# RS485_Port.net
KiCad netlist of a schematic drawn in Altium Designer
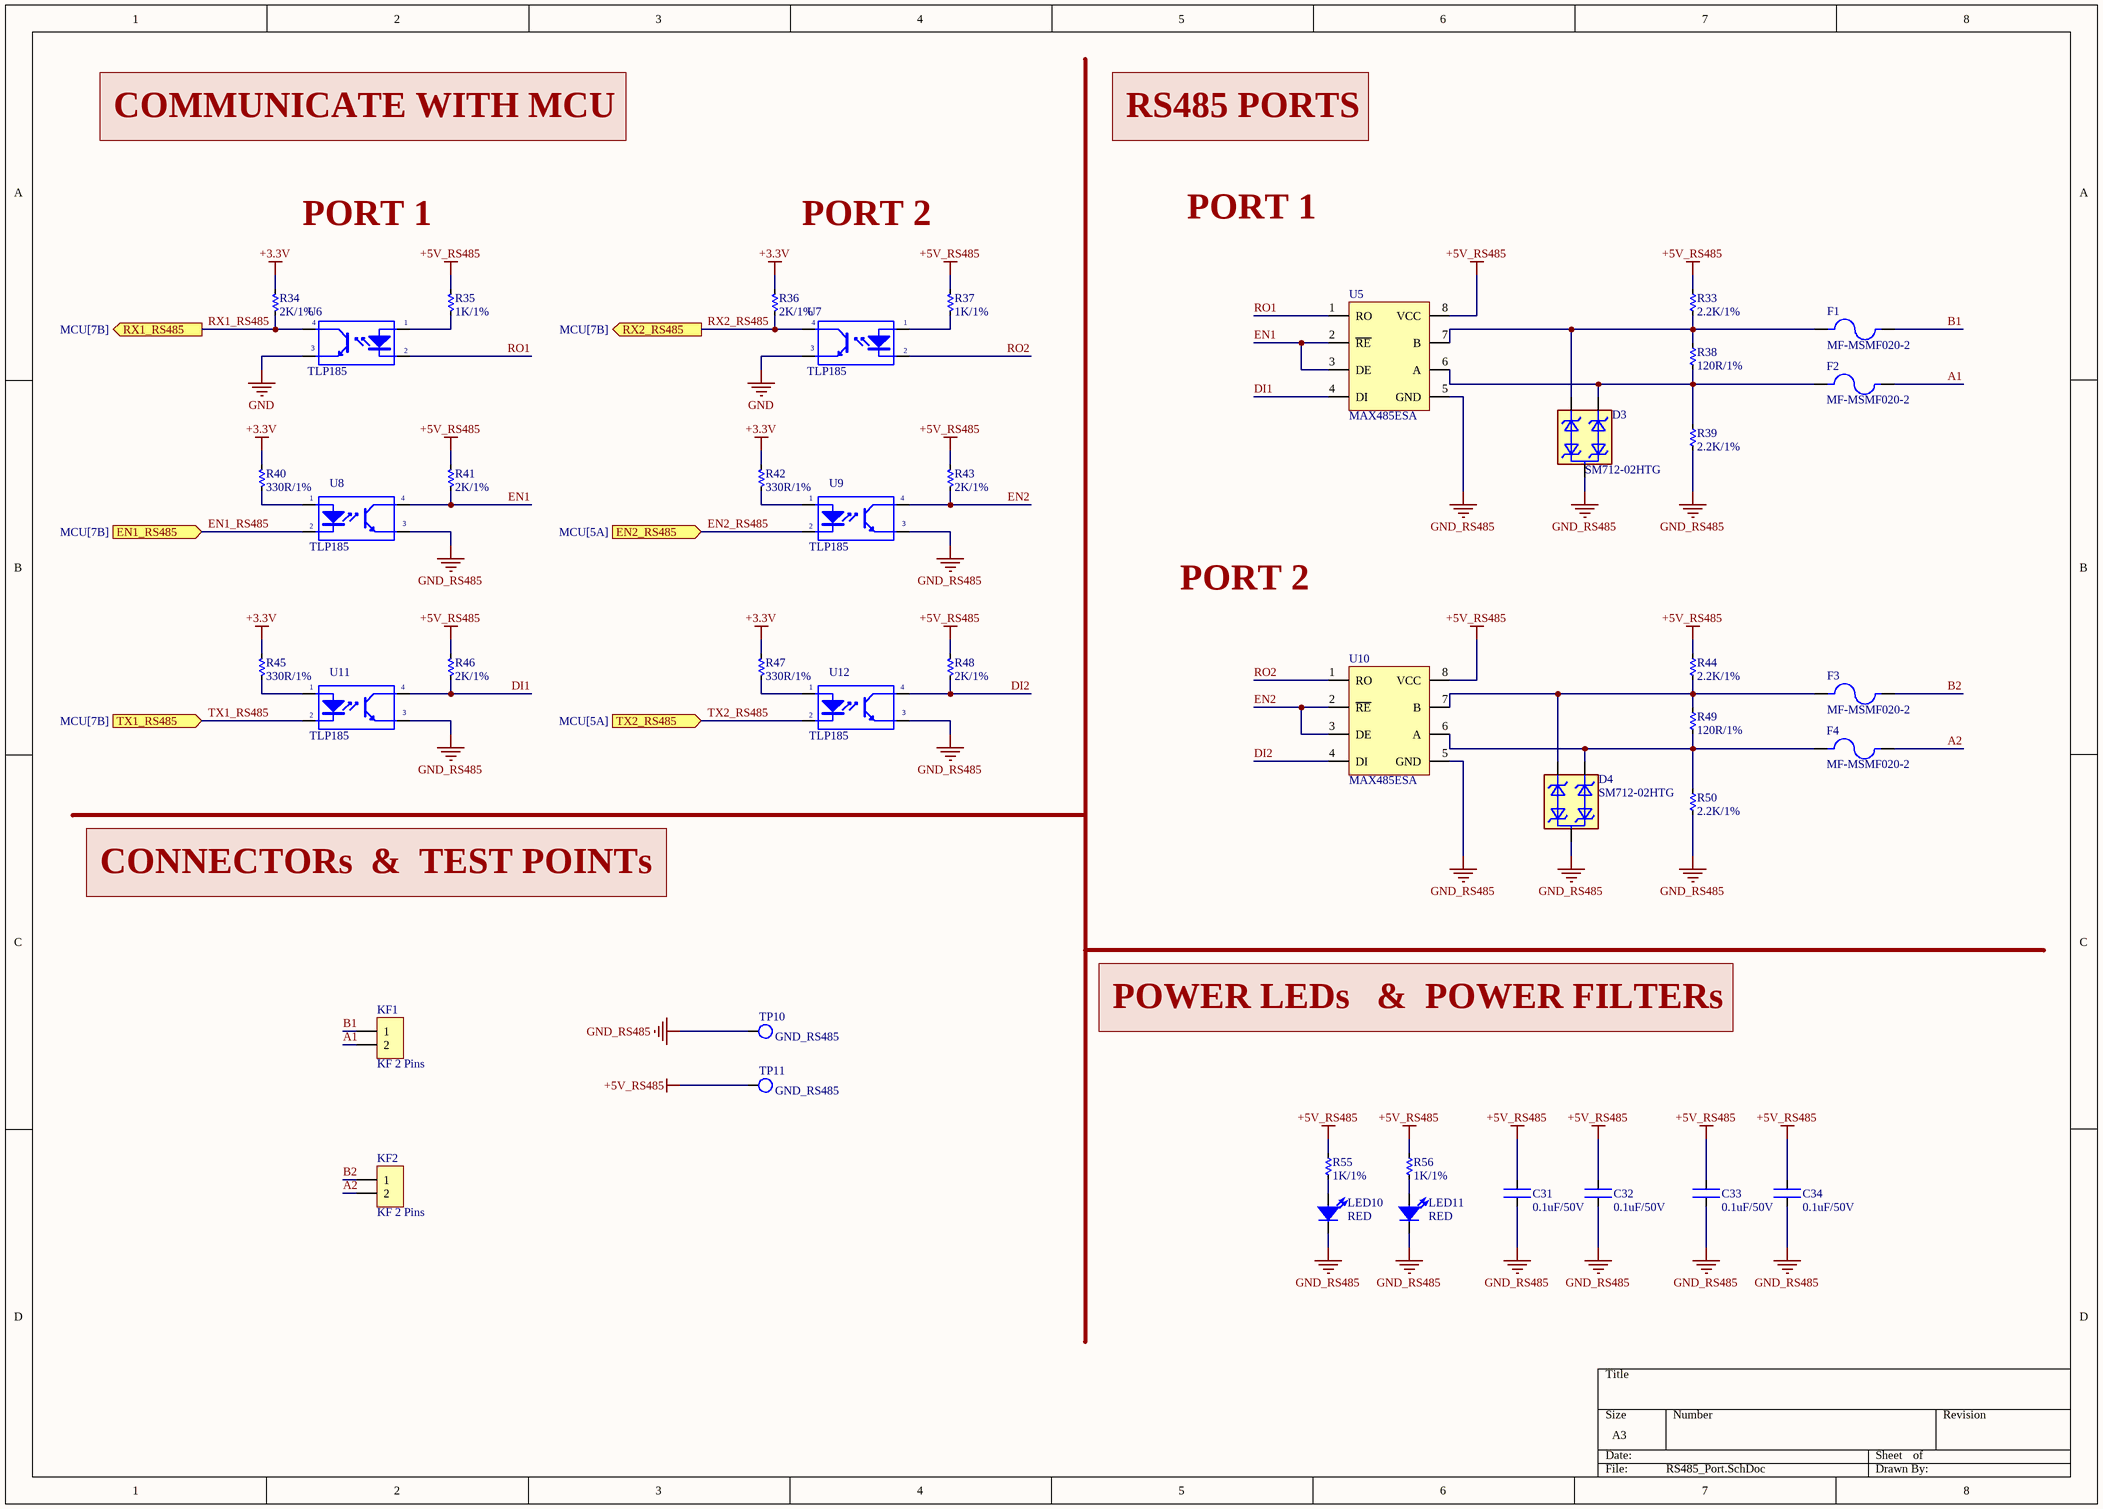
[diagram p0: RS485_Port.SchDoc]

(export (version "E")
  (design (tool "Eeschema 10.0.6"))
  (components
    (comp (ref "C31")
      (value "0.1uF/50V")
      (footprint "CAP - 0603")
      (description "CAPACITOR SMD - KEMET")
      (libsource (lib "NewLibrary") (part "CAPACITOR"))
    )
    (comp (ref "C32")
      (value "0.1uF/50V")
      (footprint "CAP - 0603")
      (description "CAPACITOR SMD - KEMET")
      (libsource (lib "NewLibrary") (part "CAPACITOR"))
    )
    (comp (ref "C33")
      (value "0.1uF/50V")
      (footprint "CAP - 0603")
      (description "CAPACITOR SMD - KEMET")
      (libsource (lib "NewLibrary") (part "CAPACITOR"))
    )
    (comp (ref "C34")
      (value "0.1uF/50V")
      (footprint "CAP - 0603")
      (description "CAPACITOR SMD - KEMET")
      (libsource (lib "NewLibrary") (part "CAPACITOR"))
    )
    (comp (ref "D3")
      (value "SM712-02HTG")
      (footprint "SOT23-3")
      (libsource (lib "NewLibrary") (part "SM712-02HTG"))
    )
    (comp (ref "D4")
      (value "SM712-02HTG")
      (footprint "SOT23-3")
      (libsource (lib "NewLibrary") (part "SM712-02HTG"))
    )
    (comp (ref "F1")
      (value "MF-MSMF020-2")
      (footprint "Fuse 4.55x3.24 mm")
      (description "Fuse Resettable 30V/0.2A; Size 4.55 x 3.24mm")
      (libsource (lib "NewLibrary") (part "MF-MSMF020-2"))
    )
    (comp (ref "F2")
      (value "MF-MSMF020-2")
      (footprint "Fuse 4.55x3.24 mm")
      (description "Fuse Resettable 30V/0.2A; Size 4.55 x 3.24mm")
      (libsource (lib "NewLibrary") (part "MF-MSMF020-2"))
    )
    (comp (ref "F3")
      (value "MF-MSMF020-2")
      (footprint "Fuse 4.55x3.24 mm")
      (description "Fuse Resettable 30V/0.2A; Size 4.55 x 3.24mm")
      (libsource (lib "NewLibrary") (part "MF-MSMF020-2"))
    )
    (comp (ref "F4")
      (value "MF-MSMF020-2")
      (footprint "Fuse 4.55x3.24 mm")
      (description "Fuse Resettable 30V/0.2A; Size 4.55 x 3.24mm")
      (libsource (lib "NewLibrary") (part "MF-MSMF020-2"))
    )
    (comp (ref "KF1")
      (value "KF 2 Pins")
      (footprint "KF-5.08-2-R")
      (description "KF Terminal Block Plug-in")
      (libsource (lib "NewLibrary") (part "KF 2 Pins"))
    )
    (comp (ref "KF2")
      (value "KF 2 Pins")
      (footprint "KF-5.08-2-R")
      (description "KF Terminal Block Plug-in")
      (libsource (lib "NewLibrary") (part "KF 2 Pins"))
    )
    (comp (ref "LED10")
      (value "RED")
      (footprint "RED_LED_0603")
      (description "LED SMD")
      (libsource (lib "NewLibrary") (part "LED_SMD"))
    )
    (comp (ref "LED11")
      (value "RED")
      (footprint "RED_LED_0603")
      (description "LED SMD")
      (libsource (lib "NewLibrary") (part "LED_SMD"))
    )
    (comp (ref "R33")
      (value "2.2K/1%")
      (footprint "RES - 0603")
      (description "Resistor SMD - YAGEO")
      (libsource (lib "NewLibrary") (part "RESISTOR"))
    )
    (comp (ref "R34")
      (value "2K/1%")
      (footprint "RES - 0603")
      (description "Resistor SMD - YAGEO")
      (libsource (lib "NewLibrary") (part "RESISTOR"))
    )
    (comp (ref "R35")
      (value "1K/1%")
      (footprint "RES - 0603")
      (description "Resistor SMD - YAGEO")
      (libsource (lib "NewLibrary") (part "RESISTOR"))
    )
    (comp (ref "R36")
      (value "2K/1%")
      (footprint "RES - 0603")
      (description "Resistor SMD - YAGEO")
      (libsource (lib "NewLibrary") (part "RESISTOR"))
    )
    (comp (ref "R37")
      (value "1K/1%")
      (footprint "RES - 0603")
      (description "Resistor SMD - YAGEO")
      (libsource (lib "NewLibrary") (part "RESISTOR"))
    )
    (comp (ref "R38")
      (value "120R/1%")
      (footprint "RES - 0603")
      (description "Resistor SMD - YAGEO")
      (libsource (lib "NewLibrary") (part "RESISTOR"))
    )
    (comp (ref "R39")
      (value "2.2K/1%")
      (footprint "RES - 0603")
      (description "Resistor SMD - YAGEO")
      (libsource (lib "NewLibrary") (part "RESISTOR"))
    )
    (comp (ref "R40")
      (value "330R/1%")
      (footprint "RES - 0603")
      (description "Resistor SMD - YAGEO")
      (libsource (lib "NewLibrary") (part "RESISTOR"))
    )
    (comp (ref "R41")
      (value "2K/1%")
      (footprint "RES - 0603")
      (description "Resistor SMD - YAGEO")
      (libsource (lib "NewLibrary") (part "RESISTOR"))
    )
    (comp (ref "R42")
      (value "330R/1%")
      (footprint "RES - 0603")
      (description "Resistor SMD - YAGEO")
      (libsource (lib "NewLibrary") (part "RESISTOR"))
    )
    (comp (ref "R43")
      (value "2K/1%")
      (footprint "RES - 0603")
      (description "Resistor SMD - YAGEO")
      (libsource (lib "NewLibrary") (part "RESISTOR"))
    )
    (comp (ref "R44")
      (value "2.2K/1%")
      (footprint "RES - 0603")
      (description "Resistor SMD - YAGEO")
      (libsource (lib "NewLibrary") (part "RESISTOR"))
    )
    (comp (ref "R45")
      (value "330R/1%")
      (footprint "RES - 0603")
      (description "Resistor SMD - YAGEO")
      (libsource (lib "NewLibrary") (part "RESISTOR"))
    )
    (comp (ref "R46")
      (value "2K/1%")
      (footprint "RES - 0603")
      (description "Resistor SMD - YAGEO")
      (libsource (lib "NewLibrary") (part "RESISTOR"))
    )
    (comp (ref "R47")
      (value "330R/1%")
      (footprint "RES - 0603")
      (description "Resistor SMD - YAGEO")
      (libsource (lib "NewLibrary") (part "RESISTOR"))
    )
    (comp (ref "R48")
      (value "2K/1%")
      (footprint "RES - 0603")
      (description "Resistor SMD - YAGEO")
      (libsource (lib "NewLibrary") (part "RESISTOR"))
    )
    (comp (ref "R49")
      (value "120R/1%")
      (footprint "RES - 0603")
      (description "Resistor SMD - YAGEO")
      (libsource (lib "NewLibrary") (part "RESISTOR"))
    )
    (comp (ref "R50")
      (value "2.2K/1%")
      (footprint "RES - 0603")
      (description "Resistor SMD - YAGEO")
      (libsource (lib "NewLibrary") (part "RESISTOR"))
    )
    (comp (ref "R55")
      (value "1K/1%")
      (footprint "RES - 0603")
      (description "Resistor SMD - YAGEO")
      (libsource (lib "NewLibrary") (part "RESISTOR"))
    )
    (comp (ref "R56")
      (value "1K/1%")
      (footprint "RES - 0603")
      (description "Resistor SMD - YAGEO")
      (libsource (lib "NewLibrary") (part "RESISTOR"))
    )
    (comp (ref "TP10")
      (value "GND_RS485")
      (footprint "Test Point")
      (description "Test Point")
      (libsource (lib "NewLibrary") (part "TEST POINT"))
    )
    (comp (ref "TP11")
      (value "GND_RS485")
      (footprint "Test Point")
      (description "Test Point")
      (libsource (lib "NewLibrary") (part "TEST POINT"))
    )
    (comp (ref "U5")
      (value "MAX485ESA")
      (footprint "SOP_8")
      (description "1/1 Transceiver Half RS422, RS485")
      (libsource (lib "NewLibrary") (part "MAX485ESA"))
    )
    (comp (ref "U6")
      (value "TLP185")
      (footprint "SOP-4")
      (description "TLP185 Optoisolator Transistor Output 3750Vrms 1 Channel 4-SOP")
      (libsource (lib "NewLibrary") (part "TLP185"))
    )
    (comp (ref "U7")
      (value "TLP185")
      (footprint "SOP-4")
      (description "TLP185 Optoisolator Transistor Output 3750Vrms 1 Channel 4-SOP")
      (libsource (lib "NewLibrary") (part "TLP185"))
    )
    (comp (ref "U8")
      (value "TLP185")
      (footprint "SOP-4")
      (description "TLP185 Optoisolator Transistor Output 3750Vrms 1 Channel 4-SOP")
      (libsource (lib "NewLibrary") (part "TLP185"))
    )
    (comp (ref "U9")
      (value "TLP185")
      (footprint "SOP-4")
      (description "TLP185 Optoisolator Transistor Output 3750Vrms 1 Channel 4-SOP")
      (libsource (lib "NewLibrary") (part "TLP185"))
    )
    (comp (ref "U10")
      (value "MAX485ESA")
      (footprint "SOP_8")
      (description "1/1 Transceiver Half RS422, RS485")
      (libsource (lib "NewLibrary") (part "MAX485ESA"))
    )
    (comp (ref "U11")
      (value "TLP185")
      (footprint "SOP-4")
      (description "TLP185 Optoisolator Transistor Output 3750Vrms 1 Channel 4-SOP")
      (libsource (lib "NewLibrary") (part "TLP185"))
    )
    (comp (ref "U12")
      (value "TLP185")
      (footprint "SOP-4")
      (description "TLP185 Optoisolator Transistor Output 3750Vrms 1 Channel 4-SOP")
      (libsource (lib "NewLibrary") (part "TLP185"))
    )
  )
  (nets
    (net (code "1") (name "+3.3V") (class "Default")
      (node (ref "R34") (pin "2") (pinfunction "2_2") (pintype "passive"))
      (node (ref "R36") (pin "2") (pinfunction "2_2") (pintype "passive"))
      (node (ref "R40") (pin "2") (pinfunction "2_2") (pintype "passive"))
      (node (ref "R42") (pin "2") (pinfunction "2_2") (pintype "passive"))
      (node (ref "R45") (pin "2") (pinfunction "2_2") (pintype "passive"))
      (node (ref "R47") (pin "2") (pinfunction "2_2") (pintype "passive"))
    )
    (net (code "2") (name "+5V_RS485") (class "Default")
      (node (ref "C31") (pin "1") (pinfunction "1_1") (pintype "passive"))
      (node (ref "C32") (pin "1") (pinfunction "1_1") (pintype "passive"))
      (node (ref "C33") (pin "1") (pinfunction "1_1") (pintype "passive"))
      (node (ref "C34") (pin "1") (pinfunction "1_1") (pintype "passive"))
      (node (ref "R33") (pin "2") (pinfunction "2_2") (pintype "passive"))
      (node (ref "R35") (pin "2") (pinfunction "2_2") (pintype "passive"))
      (node (ref "R37") (pin "2") (pinfunction "2_2") (pintype "passive"))
      (node (ref "R41") (pin "2") (pinfunction "2_2") (pintype "passive"))
      (node (ref "R43") (pin "2") (pinfunction "2_2") (pintype "passive"))
      (node (ref "R44") (pin "2") (pinfunction "2_2") (pintype "passive"))
      (node (ref "R46") (pin "2") (pinfunction "2_2") (pintype "passive"))
      (node (ref "R48") (pin "2") (pinfunction "2_2") (pintype "passive"))
      (node (ref "R55") (pin "1") (pinfunction "1_1") (pintype "passive"))
      (node (ref "R56") (pin "1") (pinfunction "1_1") (pintype "passive"))
      (node (ref "TP11") (pin "1") (pinfunction "1_1") (pintype "passive"))
      (node (ref "U10") (pin "8") (pinfunction "VCC_8") (pintype "passive"))
      (node (ref "U5") (pin "8") (pinfunction "VCC_8") (pintype "passive"))
    )
    (net (code "3") (name "/A1") (class "Default")
      (node (ref "F2") (pin "2") (pinfunction "2_2") (pintype "passive"))
      (node (ref "KF1") (pin "2") (pinfunction "2_2") (pintype "passive"))
    )
    (net (code "4") (name "/A2") (class "Default")
      (node (ref "F4") (pin "2") (pinfunction "2_2") (pintype "passive"))
      (node (ref "KF2") (pin "2") (pinfunction "2_2") (pintype "passive"))
    )
    (net (code "5") (name "/B1") (class "Default")
      (node (ref "F1") (pin "2") (pinfunction "2_2") (pintype "passive"))
      (node (ref "KF1") (pin "1") (pinfunction "1_1") (pintype "passive"))
    )
    (net (code "6") (name "/B2") (class "Default")
      (node (ref "F3") (pin "2") (pinfunction "2_2") (pintype "passive"))
      (node (ref "KF2") (pin "1") (pinfunction "1_1") (pintype "passive"))
    )
    (net (code "7") (name "/DI1") (class "Default")
      (node (ref "R46") (pin "1") (pinfunction "1_1") (pintype "passive"))
      (node (ref "U11") (pin "4") (pinfunction "C_4") (pintype "passive"))
      (node (ref "U5") (pin "4") (pinfunction "DI_4") (pintype "passive"))
    )
    (net (code "8") (name "/DI2") (class "Default")
      (node (ref "R48") (pin "1") (pinfunction "1_1") (pintype "passive"))
      (node (ref "U10") (pin "4") (pinfunction "DI_4") (pintype "passive"))
      (node (ref "U12") (pin "4") (pinfunction "C_4") (pintype "passive"))
    )
    (net (code "9") (name "/EN1") (class "Default")
      (node (ref "R41") (pin "1") (pinfunction "1_1") (pintype "passive"))
      (node (ref "U5") (pin "2") (pinfunction "~{RE}_2") (pintype "passive"))
      (node (ref "U5") (pin "3") (pinfunction "DE_3") (pintype "passive"))
      (node (ref "U8") (pin "4") (pinfunction "C_4") (pintype "passive"))
    )
    (net (code "10") (name "/EN1_RS485") (class "Default")
      (node (ref "U8") (pin "2") (pinfunction "K_2") (pintype "passive"))
    )
    (net (code "11") (name "/EN2") (class "Default")
      (node (ref "R43") (pin "1") (pinfunction "1_1") (pintype "passive"))
      (node (ref "U10") (pin "2") (pinfunction "~{RE}_2") (pintype "passive"))
      (node (ref "U10") (pin "3") (pinfunction "DE_3") (pintype "passive"))
      (node (ref "U9") (pin "4") (pinfunction "C_4") (pintype "passive"))
    )
    (net (code "12") (name "/EN2_RS485") (class "Default")
      (node (ref "U9") (pin "2") (pinfunction "K_2") (pintype "passive"))
    )
    (net (code "13") (name "/RO1") (class "Default")
      (node (ref "U5") (pin "1") (pinfunction "RO_1") (pintype "passive"))
      (node (ref "U6") (pin "2") (pinfunction "K_2") (pintype "passive"))
    )
    (net (code "14") (name "/RO2") (class "Default")
      (node (ref "U10") (pin "1") (pinfunction "RO_1") (pintype "passive"))
      (node (ref "U7") (pin "2") (pinfunction "K_2") (pintype "passive"))
    )
    (net (code "15") (name "/RX1_RS485") (class "Default")
      (node (ref "R34") (pin "1") (pinfunction "1_1") (pintype "passive"))
      (node (ref "U6") (pin "4") (pinfunction "C_4") (pintype "passive"))
    )
    (net (code "16") (name "/RX2_RS485") (class "Default")
      (node (ref "R36") (pin "1") (pinfunction "1_1") (pintype "passive"))
      (node (ref "U7") (pin "4") (pinfunction "C_4") (pintype "passive"))
    )
    (net (code "17") (name "/TX1_RS485") (class "Default")
      (node (ref "U11") (pin "2") (pinfunction "K_2") (pintype "passive"))
    )
    (net (code "18") (name "/TX2_RS485") (class "Default")
      (node (ref "U12") (pin "2") (pinfunction "K_2") (pintype "passive"))
    )
    (net (code "19") (name "GND") (class "Default")
      (node (ref "U6") (pin "3") (pinfunction "E_3") (pintype "passive"))
      (node (ref "U7") (pin "3") (pinfunction "E_3") (pintype "passive"))
    )
    (net (code "20") (name "GND_RS485") (class "Default")
      (node (ref "C31") (pin "2") (pinfunction "2_2") (pintype "passive"))
      (node (ref "C32") (pin "2") (pinfunction "2_2") (pintype "passive"))
      (node (ref "C33") (pin "2") (pinfunction "2_2") (pintype "passive"))
      (node (ref "C34") (pin "2") (pinfunction "2_2") (pintype "passive"))
      (node (ref "D3") (pin "3") (pinfunction "3_3") (pintype "passive"))
      (node (ref "D4") (pin "3") (pinfunction "3_3") (pintype "passive"))
      (node (ref "LED10") (pin "2") (pinfunction "2_2") (pintype "passive"))
      (node (ref "LED11") (pin "2") (pinfunction "2_2") (pintype "passive"))
      (node (ref "R39") (pin "1") (pinfunction "1_1") (pintype "passive"))
      (node (ref "R50") (pin "1") (pinfunction "1_1") (pintype "passive"))
      (node (ref "TP10") (pin "1") (pinfunction "1_1") (pintype "passive"))
      (node (ref "U10") (pin "5") (pinfunction "GND_5") (pintype "passive"))
      (node (ref "U11") (pin "3") (pinfunction "E_3") (pintype "passive"))
      (node (ref "U12") (pin "3") (pinfunction "E_3") (pintype "passive"))
      (node (ref "U5") (pin "5") (pinfunction "GND_5") (pintype "passive"))
      (node (ref "U8") (pin "3") (pinfunction "E_3") (pintype "passive"))
      (node (ref "U9") (pin "3") (pinfunction "E_3") (pintype "passive"))
    )
    (net (code "21") (name "Net-(LED10-Pad1)") (class "Default")
      (node (ref "LED10") (pin "1") (pinfunction "1_1") (pintype "passive"))
      (node (ref "R55") (pin "2") (pinfunction "2_2") (pintype "passive"))
    )
    (net (code "22") (name "Net-(LED11-Pad1)") (class "Default")
      (node (ref "LED11") (pin "1") (pinfunction "1_1") (pintype "passive"))
      (node (ref "R56") (pin "2") (pinfunction "2_2") (pintype "passive"))
    )
    (net (code "23") (name "Net-(U5-A)") (class "Default")
      (node (ref "D3") (pin "1") (pinfunction "1_1") (pintype "passive"))
      (node (ref "F2") (pin "1") (pinfunction "1_1") (pintype "passive"))
      (node (ref "R38") (pin "1") (pinfunction "1_1") (pintype "passive"))
      (node (ref "R39") (pin "2") (pinfunction "2_2") (pintype "passive"))
      (node (ref "U5") (pin "6") (pinfunction "A_6") (pintype "passive"))
    )
    (net (code "24") (name "Net-(U5-B)") (class "Default")
      (node (ref "D3") (pin "2") (pinfunction "2_2") (pintype "passive"))
      (node (ref "F1") (pin "1") (pinfunction "1_1") (pintype "passive"))
      (node (ref "R33") (pin "1") (pinfunction "1_1") (pintype "passive"))
      (node (ref "R38") (pin "2") (pinfunction "2_2") (pintype "passive"))
      (node (ref "U5") (pin "7") (pinfunction "B_7") (pintype "passive"))
    )
    (net (code "25") (name "Net-(U6-A)") (class "Default")
      (node (ref "R35") (pin "1") (pinfunction "1_1") (pintype "passive"))
      (node (ref "U6") (pin "1") (pinfunction "A_1") (pintype "passive"))
    )
    (net (code "26") (name "Net-(U7-A)") (class "Default")
      (node (ref "R37") (pin "1") (pinfunction "1_1") (pintype "passive"))
      (node (ref "U7") (pin "1") (pinfunction "A_1") (pintype "passive"))
    )
    (net (code "27") (name "Net-(U8-A)") (class "Default")
      (node (ref "R40") (pin "1") (pinfunction "1_1") (pintype "passive"))
      (node (ref "U8") (pin "1") (pinfunction "A_1") (pintype "passive"))
    )
    (net (code "28") (name "Net-(U9-A)") (class "Default")
      (node (ref "R42") (pin "1") (pinfunction "1_1") (pintype "passive"))
      (node (ref "U9") (pin "1") (pinfunction "A_1") (pintype "passive"))
    )
    (net (code "29") (name "Net-(U10-A)") (class "Default")
      (node (ref "D4") (pin "1") (pinfunction "1_1") (pintype "passive"))
      (node (ref "F4") (pin "1") (pinfunction "1_1") (pintype "passive"))
      (node (ref "R49") (pin "1") (pinfunction "1_1") (pintype "passive"))
      (node (ref "R50") (pin "2") (pinfunction "2_2") (pintype "passive"))
      (node (ref "U10") (pin "6") (pinfunction "A_6") (pintype "passive"))
    )
    (net (code "30") (name "Net-(U10-B)") (class "Default")
      (node (ref "D4") (pin "2") (pinfunction "2_2") (pintype "passive"))
      (node (ref "F3") (pin "1") (pinfunction "1_1") (pintype "passive"))
      (node (ref "R44") (pin "1") (pinfunction "1_1") (pintype "passive"))
      (node (ref "R49") (pin "2") (pinfunction "2_2") (pintype "passive"))
      (node (ref "U10") (pin "7") (pinfunction "B_7") (pintype "passive"))
    )
    (net (code "31") (name "Net-(U11-A)") (class "Default")
      (node (ref "R45") (pin "1") (pinfunction "1_1") (pintype "passive"))
      (node (ref "U11") (pin "1") (pinfunction "A_1") (pintype "passive"))
    )
    (net (code "32") (name "Net-(U12-A)") (class "Default")
      (node (ref "R47") (pin "1") (pinfunction "1_1") (pintype "passive"))
      (node (ref "U12") (pin "1") (pinfunction "A_1") (pintype "passive"))
    )
  )
)
